# Dev_Brd_ATSAML10D16A.net
KiCad netlist of a schematic drawn in Altium Designer
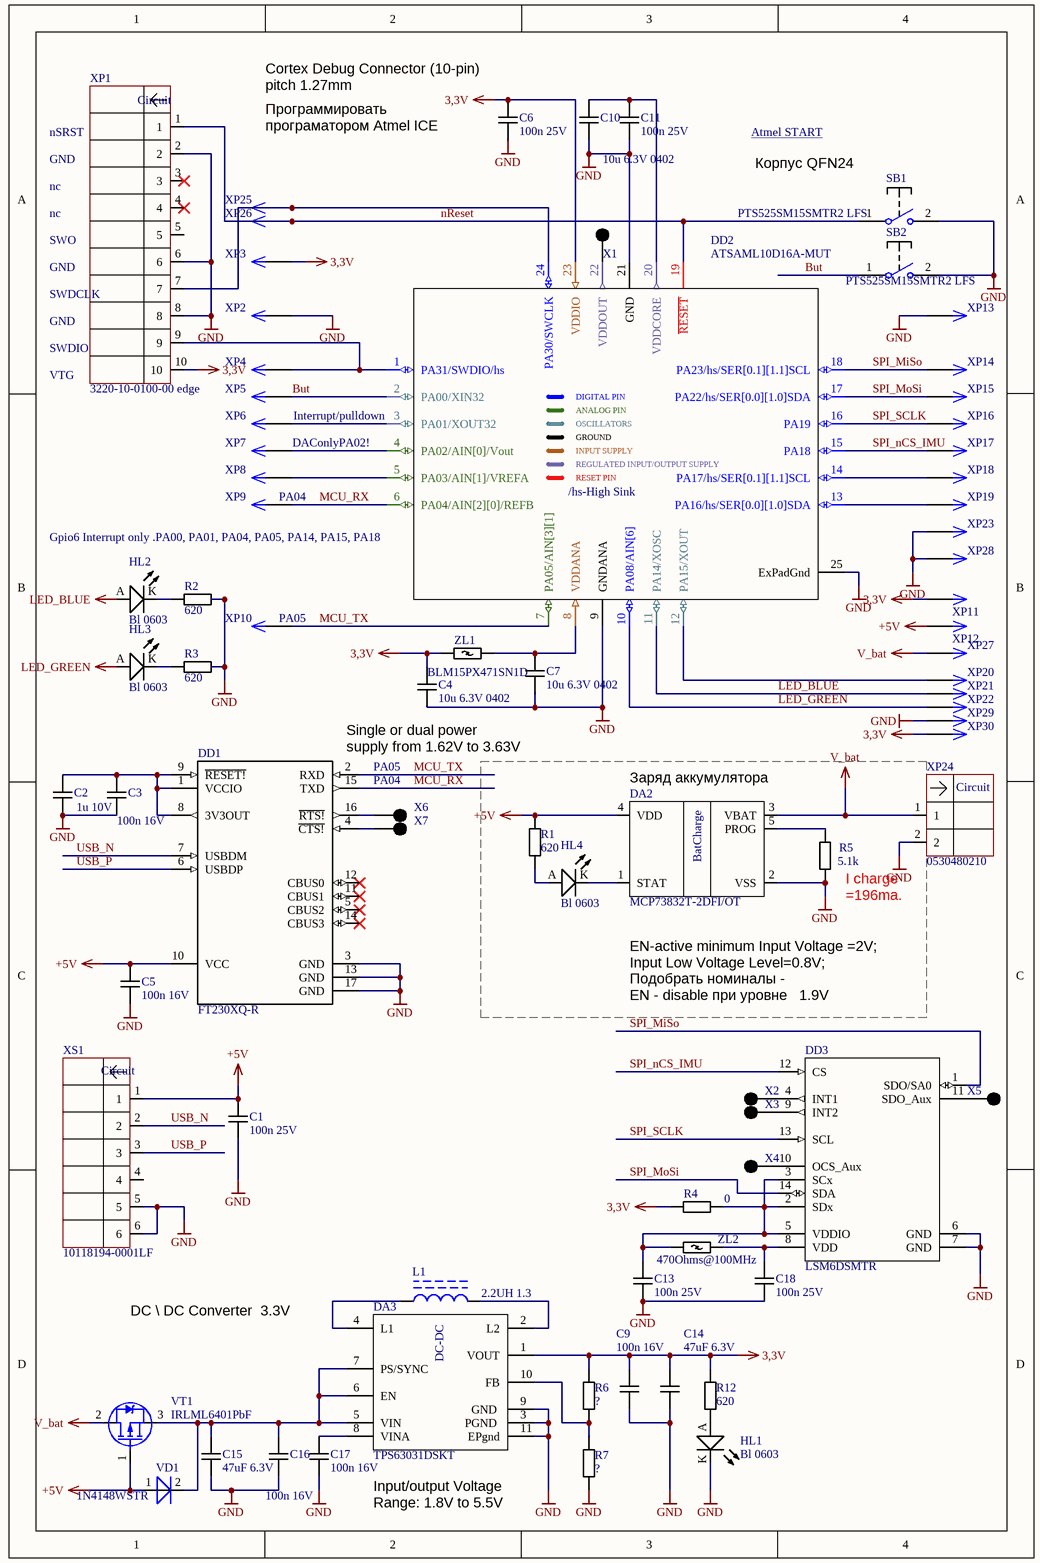
[diagram p0: Dev_Brd_ATSAML10D16A.SchDoc]

(export (version "E")
  (design (tool "Eeschema 10.0.6"))
  (components
    (comp (ref "C1")
      (value "100n 25V")
      (footprint "CapKemet1005(0402)")
      (description "CAP CER 0.1UF 25V X5R 0402")
      (fields
        (field (name "PART NUMBER") "CAPC1608(0603)")
        (field (name "DIGI-KEY PART NUMBER") "732-7495-1-ND")
      )
      (libsource (lib "") (part "Cap_1"))
    )
    (comp (ref "C2")
      (value "1u 10V")
      (footprint "CapKemet1005(0402)")
      (description "CAP CER 1UF 10V 10% X6S 0402")
      (fields
        (field (name "PART NUMBER") "CAPC1005(0402)N")
        (field (name "MANUFACTURER PART NUMBER") "LMK105BJ105KPLF")
      )
      (libsource (lib "") (part "Cap_1"))
    )
    (comp (ref "C3")
      (value "100n 16V")
      (footprint "CapKemet1005(0402)")
      (description "Cap Cer 0.1uF 16V 1% C0G(NP0) MLCC")
      (fields
        (field (name "PART NUMBER") "CL05F104ZO5NNNC")
        (field (name "DIGI-KEY PART NUMBER") "1276-1004-1-ND")
      )
      (libsource (lib "SssAccesDatbase") (part "Cap"))
    )
    (comp (ref "C4")
      (value "10u 6.3V 0402")
      (footprint "CapKemet1005(0402)")
      (description "CAP CER 10UF 6.3V X5R 0402")
      (fields
        (field (name "PART NUMBER") "CAPC1608(0603)")
        (field (name "DIGI-KEY PART NUMBER") "GRJ155R60J106ME11D")
      )
      (libsource (lib "SssAccesDatbase") (part "Cap"))
    )
    (comp (ref "C5")
      (value "100n 16V")
      (footprint "CapKemet1005(0402)")
      (description "Cap Cer 0.1uF 16V 1% C0G(NP0) MLCC")
      (fields
        (field (name "PART NUMBER") "CL05F104ZO5NNNC")
        (field (name "DIGI-KEY PART NUMBER") "1276-1004-1-ND")
      )
      (libsource (lib "SssAccesDatbase") (part "Cap"))
    )
    (comp (ref "C6")
      (value "100n 25V")
      (footprint "CapKemet1005(0402)")
      (description "CAP CER 0.1UF 25V X5R 0402")
      (fields
        (field (name "PART NUMBER") "CAPC1608(0603)")
        (field (name "DIGI-KEY PART NUMBER") "732-7495-1-ND")
      )
      (libsource (lib "") (part "Cap_1"))
    )
    (comp (ref "C7")
      (value "10u 6.3V 0402")
      (footprint "CapKemet1005(0402)")
      (description "CAP CER 10UF 6.3V X5R 0402")
      (fields
        (field (name "PART NUMBER") "CAPC1608(0603)")
        (field (name "DIGI-KEY PART NUMBER") "GRJ155R60J106ME11D")
      )
      (libsource (lib "SssAccesDatbase") (part "Cap"))
    )
    (comp (ref "C9")
      (value "100n 16V")
      (footprint "CapKemet1005(0402)")
      (description "Cap Cer 0.1uF 16V 1% C0G(NP0) MLCC")
      (fields
        (field (name "PART NUMBER") "CL05F104ZO5NNNC")
        (field (name "DIGI-KEY PART NUMBER") "1276-1004-1-ND")
      )
      (libsource (lib "SssAccesDatbase") (part "Cap"))
    )
    (comp (ref "C10")
      (value "10u 6.3V 0402")
      (footprint "CapKemet1005(0402)")
      (description "CAP CER 10UF 6.3V X5R 0402")
      (fields
        (field (name "PART NUMBER") "CAPC1608(0603)")
        (field (name "DIGI-KEY PART NUMBER") "GRJ155R60J106ME11D")
      )
      (libsource (lib "SssAccesDatbase") (part "Cap"))
    )
    (comp (ref "C11")
      (value "100n 25V")
      (footprint "CapKemet1005(0402)")
      (description "CAP CER 0.1UF 25V X5R 0402")
      (fields
        (field (name "PART NUMBER") "CAPC1608(0603)")
        (field (name "DIGI-KEY PART NUMBER") "732-7495-1-ND")
      )
      (libsource (lib "") (part "Cap_1"))
    )
    (comp (ref "C13")
      (value "100n 25V")
      (footprint "CapKemet1005(0402)")
      (description "CAP CER 0.1UF 25V X7R 0402")
      (fields
        (field (name "PART NUMBER") "CL05B104KA5NNNC")
        (field (name "DIGI-KEY PART NUMBER") "1276-6720-1-ND")
      )
      (libsource (lib "SssAccesDatbase") (part "Cap"))
    )
    (comp (ref "C14")
      (value "47uF 6.3V")
      (footprint "CapKemet1005(0402)")
      (description "CAP CER 47UF 6.3V X5R 0603")
      (fields
        (field (name "PART NUMBER") "GRM188R60J476ME15D")
        (field (name "DIGI-KEY PART NUMBER") "490-13247-1-ND")
      )
      (libsource (lib "SssAccesDatbase") (part "Cap"))
    )
    (comp (ref "C15")
      (value "47uF 6.3V")
      (footprint "CapKemet1005(0402)")
      (description "CAP CER 47UF 6.3V X5R 0603")
      (fields
        (field (name "PART NUMBER") "GRM188R60J476ME15D")
        (field (name "DIGI-KEY PART NUMBER") "490-13247-1-ND")
      )
      (libsource (lib "SssAccesDatbase") (part "Cap"))
    )
    (comp (ref "C16")
      (value "100n 16V")
      (footprint "CapKemet1005(0402)")
      (description "Cap Cer 0.1uF 16V 1% C0G(NP0) MLCC")
      (fields
        (field (name "PART NUMBER") "CL05F104ZO5NNNC")
        (field (name "DIGI-KEY PART NUMBER") "1276-1004-1-ND")
      )
      (libsource (lib "SssAccesDatbase") (part "Cap"))
    )
    (comp (ref "C17")
      (value "100n 16V")
      (footprint "CapKemet1005(0402)")
      (description "Cap Cer 0.1uF 16V 1% C0G(NP0) MLCC")
      (fields
        (field (name "PART NUMBER") "CL05F104ZO5NNNC")
        (field (name "DIGI-KEY PART NUMBER") "1276-1004-1-ND")
      )
      (libsource (lib "SssAccesDatbase") (part "Cap"))
    )
    (comp (ref "C18")
      (value "100n 25V")
      (footprint "CapKemet1005(0402)")
      (description "CAP CER 0.1UF 25V X7R 0402")
      (fields
        (field (name "PART NUMBER") "CL05B104KA5NNNC")
        (field (name "DIGI-KEY PART NUMBER") "1276-6720-1-ND")
      )
      (libsource (lib "SssAccesDatbase") (part "Cap"))
    )
    (comp (ref "DA2")
      (value "MCP73832T-2DFI/OT")
      (footprint "SOT-23-5")
      (description "IC LI-ION/LI-POLY CTRLR SOT23-5")
      (fields (field (name "DIGI-KEY PART NUMBER") "MCP73832T-2DFI/OTCT-ND"))
      (libsource (lib "SssAccesDatbase") (part "MCP73832T-2DFI/OT"))
    )
    (comp (ref "DA3")
      (value "TPS63031DSKT")
      (footprint "WSON-10")
      (description "IC REG BCK BST 3.3V 900MA 10SON")
      (fields (field (name "DIGI-KEY PART NUMBER") "296-23904-1-ND"))
      (libsource (lib "SssAccesDatbase") (part "TPS63031DSKR"))
    )
    (comp (ref "DD1")
      (value "FT230XQ-R")
      (footprint "QFN-16(4x4)")
      (description "IC USB SERIAL BASIC UART 16QFN")
      (fields (field (name "DIGI-KEY PART NUMBER") "768-1130-1-ND"))
      (libsource (lib "SssAccesDatbase") (part "FT230XQ-R"))
    )
    (comp (ref "DD2")
      (value "ATSAML10D16A-MUT")
      (footprint "VQFN-24")
      (description "IC MCU 32BIT 64KB FLASH 24VQFN,ARM® Cortex®-M23")
      (fields (field (name "DIGI-KEY PART NUMBER") "ATSAML10D16A-MUTCT-ND"))
      (libsource (lib "SssAccesDatbase") (part "ATSAML10D16A-MUT"))
    )
    (comp (ref "DD3")
      (value "LSM6DSMTR")
      (footprint "LGA-14L_2P5X3X0P83_STM-M")
      (description "IMU ACCEL/GYRO I2C/SPI 14LGA")
      (fields
        (field (name "DIGI-KEY PART NUMBER") "497-16696-1-ND")
        (field (name "MOUSER PART NUMBER") "511-LSM6DSMTR")
        (field (name "COPYRIGHT") "Copyright (C) 2018 Accelerated Designs. All rights reserved")
      )
      (libsource (lib "SssAccesDatbase") (part "LSM6DSMTR"))
    )
    (comp (ref "HL1")
      (value "Bl 0603")
      (footprint "LED-0603-BLUE")
      (description "LED BLUE DIFFUSED 0603 SMD")
      (fields
        (field (name "PART NUMBER") "150060BS55040")
        (field (name "DIGI-KEY PART NUMBER") "732-12013-1-ND")
      )
      (libsource (lib "SssAccesDatbase") (part "LED_AK"))
    )
    (comp (ref "HL2")
      (value "Bl 0603")
      (footprint "LED-0603-BLUE")
      (description "LED BLUE DIFFUSED 0603 SMD")
      (fields
        (field (name "PART NUMBER") "150060BS55040")
        (field (name "DIGI-KEY PART NUMBER") "732-12013-1-ND")
      )
      (libsource (lib "SssAccesDatbase") (part "LED_AK"))
    )
    (comp (ref "HL3")
      (value "Bl 0603")
      (footprint "LED-0603-BLUE")
      (description "LED BLUE DIFFUSED 0603 SMD")
      (fields
        (field (name "PART NUMBER") "150060BS55040")
        (field (name "DIGI-KEY PART NUMBER") "732-12013-1-ND")
      )
      (libsource (lib "SssAccesDatbase") (part "LED_AK"))
    )
    (comp (ref "HL4")
      (value "Bl 0603")
      (footprint "LED-0603-BLUE")
      (description "LED BLUE DIFFUSED 0603 SMD")
      (fields
        (field (name "PART NUMBER") "150060BS55040")
        (field (name "DIGI-KEY PART NUMBER") "732-12013-1-ND")
      )
      (libsource (lib "SssAccesDatbase") (part "LED_AK"))
    )
    (comp (ref "L1")
      (value "2.2UH 1.3")
      (footprint "CDRH2D11")
      (description "FIXED IND 2.2UH 1.3A 120 MOHM")
      (fields
        (field (name "PART NUMBER") "CDRH2D11/HPNP-2R2NC")
        (field (name "DIGI-KEY PART NUMBER") "308-1578-1-ND")
        (field (name "PUBLISHER") "Altium Limited")
      )
      (libsource (lib "SssAccesDatbase") (part "Inductor ferrite"))
    )
    (comp (ref "R1")
      (value "620")
      (footprint "REZKemet 0402")
      (fields (field (name "PART NUMBER") "RESC1005(0402)"))
      (libsource (lib "SssAccesDatbase") (part "Resistor general"))
    )
    (comp (ref "R2")
      (value "620")
      (footprint "REZKemet 0402")
      (fields (field (name "PART NUMBER") "RESC1005(0402)"))
      (libsource (lib "") (part "Resistor general_1"))
    )
    (comp (ref "R3")
      (value "620")
      (footprint "REZKemet 0402")
      (fields (field (name "PART NUMBER") "RESC1005(0402)"))
      (libsource (lib "") (part "Resistor general_1"))
    )
    (comp (ref "R4")
      (value "0")
      (footprint "REZKemet 0402")
      (description "RES SMD 0402 0 Ohm")
      (fields
        (field (name "PART NUMBER") "RMCF0402ZT0R00")
        (field (name "MOUSER PART NUMBER") "RMCF0402ZT0R00CT-ND")
      )
      (libsource (lib "") (part "Resistor general_1"))
    )
    (comp (ref "R5")
      (value "5.1k")
      (footprint "REZKemet 0402")
      (description "RES SMD 5.1K OHM 1% 1/10W 0402")
      (fields
        (field (name "PART NUMBER") "RESC1005(0402)")
        (field (name "MANUFACTURER PART NUMBER") "ERJ-2RKF5101X")
      )
      (libsource (lib "") (part "Resistor general_2"))
    )
    (comp (ref "R6")
      (value "?")
      (footprint "REZKemet 0402")
      (fields (field (name "PART NUMBER") "RESC1005(0402)"))
      (libsource (lib "SssAccesDatbase") (part "Resistor general"))
    )
    (comp (ref "R7")
      (value "?")
      (footprint "REZKemet 0402")
      (fields (field (name "PART NUMBER") "RESC1005(0402)"))
      (libsource (lib "SssAccesDatbase") (part "Resistor general"))
    )
    (comp (ref "R12")
      (value "620")
      (footprint "REZKemet 0402")
      (fields (field (name "PART NUMBER") "RESC1005(0402)"))
      (libsource (lib "SssAccesDatbase") (part "Resistor general"))
    )
    (comp (ref "SB1")
      (value "PTS525SM15SMTR2 LFS")
      (footprint "TACT_SWITCH KPT1187B")
      (description "SWITCH TACTILE SPST-NO 0.02A 15V")
      (fields (field (name "DIGI-KEY PART NUMBER") "CKN9104CT-ND"))
      (libsource (lib "SssAccesDatbase") (part "TACT_SWITCH KPT1187B"))
    )
    (comp (ref "SB2")
      (value "PTS525SM15SMTR2 LFS")
      (footprint "TACT_SWITCH KPT1187B")
      (description "SWITCH TACTILE SPST-NO 0.02A 15V")
      (fields (field (name "DIGI-KEY PART NUMBER") "CKN9104CT-ND"))
      (libsource (lib "SssAccesDatbase") (part "TACT_SWITCH KPT1187B"))
    )
    (comp (ref "VD1")
      (value "1N4148WSTR")
      (footprint "SOD323")
      (description "DIODE GEN PURP 75V 300MA SOD323")
      (fields
        (field (name "DIGI-KEY PART NUMBER") "1655-1359-1-ND")
        (field (name "MANUFACTURER PART NUMBER") "?")
        (field (name "PUBLISHER") "Altium Limited")
      )
      (libsource (lib "SssAccesDatbase") (part "Diode"))
    )
    (comp (ref "VT1")
      (value "IRLML6401PbF")
      (footprint "SOT23-3N")
      (fields (field (name "DIGI-KEY PART NUMBER") "???"))
      (libsource (lib "SssAccesDatbase") (part "TRANS-P-Channel-GDS"))
    )
    (comp (ref "X1")
      (value "PLLS1.27-1-TOP-R")
      (footprint "PLLS1.27-1-TOP-R")
      (libsource (lib "SssAccesDatbase") (part "X1_1"))
    )
    (comp (ref "X2")
      (value "PLLS1.27-1-TOP-R")
      (footprint "PLLS1.27-1-TOP-R")
      (libsource (lib "SssAccesDatbase") (part "X1_1"))
    )
    (comp (ref "X3")
      (value "PLLS1.27-1-TOP-R")
      (footprint "PLLS1.27-1-TOP-R")
      (libsource (lib "SssAccesDatbase") (part "X1_1"))
    )
    (comp (ref "X4")
      (value "PLLS1.27-1-TOP-R")
      (footprint "PLLS1.27-1-TOP-R")
      (libsource (lib "SssAccesDatbase") (part "X1_1"))
    )
    (comp (ref "X5")
      (value "PLLS1.27-1-TOP-R")
      (footprint "PLLS1.27-1-TOP-R")
      (libsource (lib "SssAccesDatbase") (part "X1_1"))
    )
    (comp (ref "X6")
      (value "PLLS1.27-1-TOP-R")
      (footprint "PLLS1.27-1-TOP-R")
      (libsource (lib "SssAccesDatbase") (part "X1_1"))
    )
    (comp (ref "X7")
      (value "PLLS1.27-1-TOP-R")
      (footprint "PLLS1.27-1-TOP-R")
      (libsource (lib "SssAccesDatbase") (part "X1_1"))
    )
    (comp (ref "XP1")
      (value "3220-10-0100-00 edge")
      (footprint "IPS 10(1.27)edge")
      (description "3220-10-0100-00")
      (fields (field (name "DIGI-KEY PART NUMBER") "1175-1627-ND"))
      (libsource (lib "SssAccesDatbase") (part "XP-10"))
    )
    (comp (ref "XP2")
      (value "PLS-1")
      (footprint "PLS-1-3D")
      (description "CONN HEADER VERT 1POS")
      (fields
        (field (name "DIGI-KEY PART NUMBER") "S1011EC-01-ND")
        (field (name "MANUFACTURER PART NUMBER") "PRPC001SAAN-RC")
      )
      (libsource (lib "SssAccesDatbase") (part "XP-1_1"))
    )
    (comp (ref "XP3")
      (value "PLS-1")
      (footprint "PLS-1-3D")
      (description "CONN HEADER VERT 1POS")
      (fields
        (field (name "DIGI-KEY PART NUMBER") "S1011EC-01-ND")
        (field (name "MANUFACTURER PART NUMBER") "PRPC001SAAN-RC")
      )
      (libsource (lib "SssAccesDatbase") (part "XP-1_1"))
    )
    (comp (ref "XP4")
      (value "PLS-1")
      (footprint "PLS-1-3D")
      (description "CONN HEADER VERT 1POS")
      (fields
        (field (name "DIGI-KEY PART NUMBER") "S1011EC-01-ND")
        (field (name "MANUFACTURER PART NUMBER") "PRPC001SAAN-RC")
      )
      (libsource (lib "SssAccesDatbase") (part "XP-1_1"))
    )
    (comp (ref "XP5")
      (value "PLS-1")
      (footprint "PLS-1-3D")
      (description "CONN HEADER VERT 1POS")
      (fields
        (field (name "DIGI-KEY PART NUMBER") "S1011EC-01-ND")
        (field (name "MANUFACTURER PART NUMBER") "PRPC001SAAN-RC")
      )
      (libsource (lib "SssAccesDatbase") (part "XP-1_1"))
    )
    (comp (ref "XP6")
      (value "PLS-1")
      (footprint "PLS-1-3D")
      (description "CONN HEADER VERT 1POS")
      (fields
        (field (name "DIGI-KEY PART NUMBER") "S1011EC-01-ND")
        (field (name "MANUFACTURER PART NUMBER") "PRPC001SAAN-RC")
      )
      (libsource (lib "SssAccesDatbase") (part "XP-1_1"))
    )
    (comp (ref "XP7")
      (value "PLS-1")
      (footprint "PLS-1-3D")
      (description "CONN HEADER VERT 1POS")
      (fields
        (field (name "DIGI-KEY PART NUMBER") "S1011EC-01-ND")
        (field (name "MANUFACTURER PART NUMBER") "PRPC001SAAN-RC")
      )
      (libsource (lib "SssAccesDatbase") (part "XP-1_1"))
    )
    (comp (ref "XP8")
      (value "PLS-1")
      (footprint "PLS-1-3D")
      (description "CONN HEADER VERT 1POS")
      (fields
        (field (name "DIGI-KEY PART NUMBER") "S1011EC-01-ND")
        (field (name "MANUFACTURER PART NUMBER") "PRPC001SAAN-RC")
      )
      (libsource (lib "SssAccesDatbase") (part "XP-1_1"))
    )
    (comp (ref "XP9")
      (value "PLS-1")
      (footprint "PLS-1-3D")
      (description "CONN HEADER VERT 1POS")
      (fields
        (field (name "DIGI-KEY PART NUMBER") "S1011EC-01-ND")
        (field (name "MANUFACTURER PART NUMBER") "PRPC001SAAN-RC")
      )
      (libsource (lib "SssAccesDatbase") (part "XP-1_1"))
    )
    (comp (ref "XP10")
      (value "PLS-1")
      (footprint "PLS-1-3D")
      (description "CONN HEADER VERT 1POS")
      (fields
        (field (name "DIGI-KEY PART NUMBER") "S1011EC-01-ND")
        (field (name "MANUFACTURER PART NUMBER") "PRPC001SAAN-RC")
      )
      (libsource (lib "SssAccesDatbase") (part "XP-1_1"))
    )
    (comp (ref "XP11")
      (value "PLS-1")
      (footprint "PLS-1-3D")
      (description "CONN HEADER VERT 1POS")
      (fields
        (field (name "DIGI-KEY PART NUMBER") "S1011EC-01-ND")
        (field (name "MANUFACTURER PART NUMBER") "PRPC001SAAN-RC")
      )
      (libsource (lib "SssAccesDatbase") (part "XP-1_1"))
    )
    (comp (ref "XP12")
      (value "PLS-1")
      (footprint "PLS-1-3D")
      (description "CONN HEADER VERT 1POS")
      (fields
        (field (name "DIGI-KEY PART NUMBER") "S1011EC-01-ND")
        (field (name "MANUFACTURER PART NUMBER") "PRPC001SAAN-RC")
      )
      (libsource (lib "SssAccesDatbase") (part "XP-1_1"))
    )
    (comp (ref "XP13")
      (value "PLS-1")
      (footprint "PLS-1-3D")
      (description "CONN HEADER VERT 1POS")
      (fields
        (field (name "DIGI-KEY PART NUMBER") "S1011EC-01-ND")
        (field (name "MANUFACTURER PART NUMBER") "PRPC001SAAN-RC")
      )
      (libsource (lib "SssAccesDatbase") (part "XP-1_1"))
    )
    (comp (ref "XP14")
      (value "PLS-1")
      (footprint "PLS-1-3D")
      (description "CONN HEADER VERT 1POS")
      (fields
        (field (name "DIGI-KEY PART NUMBER") "S1011EC-01-ND")
        (field (name "MANUFACTURER PART NUMBER") "PRPC001SAAN-RC")
      )
      (libsource (lib "SssAccesDatbase") (part "XP-1_1"))
    )
    (comp (ref "XP15")
      (value "PLS-1")
      (footprint "PLS-1-3D")
      (description "CONN HEADER VERT 1POS")
      (fields
        (field (name "DIGI-KEY PART NUMBER") "S1011EC-01-ND")
        (field (name "MANUFACTURER PART NUMBER") "PRPC001SAAN-RC")
      )
      (libsource (lib "SssAccesDatbase") (part "XP-1_1"))
    )
    (comp (ref "XP16")
      (value "PLS-1")
      (footprint "PLS-1-3D")
      (description "CONN HEADER VERT 1POS")
      (fields
        (field (name "DIGI-KEY PART NUMBER") "S1011EC-01-ND")
        (field (name "MANUFACTURER PART NUMBER") "PRPC001SAAN-RC")
      )
      (libsource (lib "SssAccesDatbase") (part "XP-1_1"))
    )
    (comp (ref "XP17")
      (value "PLS-1")
      (footprint "PLS-1-3D")
      (description "CONN HEADER VERT 1POS")
      (fields
        (field (name "DIGI-KEY PART NUMBER") "S1011EC-01-ND")
        (field (name "MANUFACTURER PART NUMBER") "PRPC001SAAN-RC")
      )
      (libsource (lib "SssAccesDatbase") (part "XP-1_1"))
    )
    (comp (ref "XP18")
      (value "PLS-1")
      (footprint "PLS-1-3D")
      (description "CONN HEADER VERT 1POS")
      (fields
        (field (name "DIGI-KEY PART NUMBER") "S1011EC-01-ND")
        (field (name "MANUFACTURER PART NUMBER") "PRPC001SAAN-RC")
      )
      (libsource (lib "SssAccesDatbase") (part "XP-1_1"))
    )
    (comp (ref "XP19")
      (value "PLS-1")
      (footprint "PLS-1-3D")
      (description "CONN HEADER VERT 1POS")
      (fields
        (field (name "DIGI-KEY PART NUMBER") "S1011EC-01-ND")
        (field (name "MANUFACTURER PART NUMBER") "PRPC001SAAN-RC")
      )
      (libsource (lib "SssAccesDatbase") (part "XP-1_1"))
    )
    (comp (ref "XP20")
      (value "PLS-1")
      (footprint "PLS-1-3D")
      (description "CONN HEADER VERT 1POS")
      (fields
        (field (name "DIGI-KEY PART NUMBER") "S1011EC-01-ND")
        (field (name "MANUFACTURER PART NUMBER") "PRPC001SAAN-RC")
      )
      (libsource (lib "SssAccesDatbase") (part "XP-1_1"))
    )
    (comp (ref "XP21")
      (value "PLS-1")
      (footprint "PLS-1-3D")
      (description "CONN HEADER VERT 1POS")
      (fields
        (field (name "DIGI-KEY PART NUMBER") "S1011EC-01-ND")
        (field (name "MANUFACTURER PART NUMBER") "PRPC001SAAN-RC")
      )
      (libsource (lib "SssAccesDatbase") (part "XP-1_1"))
    )
    (comp (ref "XP22")
      (value "PLS-1")
      (footprint "PLS-1-3D")
      (description "CONN HEADER VERT 1POS")
      (fields
        (field (name "DIGI-KEY PART NUMBER") "S1011EC-01-ND")
        (field (name "MANUFACTURER PART NUMBER") "PRPC001SAAN-RC")
      )
      (libsource (lib "SssAccesDatbase") (part "XP-1_1"))
    )
    (comp (ref "XP23")
      (value "PLS-1")
      (footprint "PLS-1-3D")
      (description "CONN HEADER VERT 1POS")
      (fields
        (field (name "DIGI-KEY PART NUMBER") "S1011EC-01-ND")
        (field (name "MANUFACTURER PART NUMBER") "PRPC001SAAN-RC")
      )
      (libsource (lib "SssAccesDatbase") (part "XP-1_1"))
    )
    (comp (ref "XP24")
      (value "0530480210")
      (footprint "0530480210")
      (description "CONN HEADER R/A 2POS 1.25MM")
      (fields (field (name "DIGI-KEY PART NUMBER") "WM1742-ND"))
      (libsource (lib "SssAccesDatbase") (part "XP-2"))
    )
    (comp (ref "XP25")
      (value "PLS-1")
      (footprint "PLS-1-3D")
      (description "CONN HEADER VERT 1POS")
      (fields
        (field (name "DIGI-KEY PART NUMBER") "S1011EC-01-ND")
        (field (name "MANUFACTURER PART NUMBER") "PRPC001SAAN-RC")
      )
      (libsource (lib "SssAccesDatbase") (part "XP-1_1"))
    )
    (comp (ref "XP26")
      (value "PLS-1")
      (footprint "PLS-1-3D")
      (description "CONN HEADER VERT 1POS")
      (fields
        (field (name "DIGI-KEY PART NUMBER") "S1011EC-01-ND")
        (field (name "MANUFACTURER PART NUMBER") "PRPC001SAAN-RC")
      )
      (libsource (lib "SssAccesDatbase") (part "XP-1_1"))
    )
    (comp (ref "XP27")
      (value "PLS-1")
      (footprint "PLS-1-3D")
      (description "CONN HEADER VERT 1POS")
      (fields
        (field (name "DIGI-KEY PART NUMBER") "S1011EC-01-ND")
        (field (name "MANUFACTURER PART NUMBER") "PRPC001SAAN-RC")
      )
      (libsource (lib "SssAccesDatbase") (part "XP-1_1"))
    )
    (comp (ref "XP28")
      (value "PLS-1")
      (footprint "PLS-1-3D")
      (description "CONN HEADER VERT 1POS")
      (fields
        (field (name "DIGI-KEY PART NUMBER") "S1011EC-01-ND")
        (field (name "MANUFACTURER PART NUMBER") "PRPC001SAAN-RC")
      )
      (libsource (lib "SssAccesDatbase") (part "XP-1_1"))
    )
    (comp (ref "XP29")
      (value "PLS-1")
      (footprint "PLS-1-3D")
      (description "CONN HEADER VERT 1POS")
      (fields
        (field (name "DIGI-KEY PART NUMBER") "S1011EC-01-ND")
        (field (name "MANUFACTURER PART NUMBER") "PRPC001SAAN-RC")
      )
      (libsource (lib "SssAccesDatbase") (part "XP-1_1"))
    )
    (comp (ref "XP30")
      (value "PLS-1")
      (footprint "PLS-1-3D")
      (description "CONN HEADER VERT 1POS")
      (fields
        (field (name "DIGI-KEY PART NUMBER") "S1011EC-01-ND")
        (field (name "MANUFACTURER PART NUMBER") "PRPC001SAAN-RC")
      )
      (libsource (lib "SssAccesDatbase") (part "XP-1_1"))
    )
    (comp (ref "XS1")
      (value "10118194-0001LF")
      (footprint "MICRO_USB _B")
      (description "USB Connectors 5P MICRO USB TYPE B RCPT W/ REAR PEGS")
      (fields
        (field (name "DIGI-KEY PART NUMBER") "609-4618-1-ND")
        (field (name "MOUSER PART NUMBER") "649-10118194-0001LF")
      )
      (libsource (lib "SssAccesDatbase") (part "Micro USB"))
    )
    (comp (ref "ZL1")
      (value "BLM15PX471SN1D")
      (footprint "Ferrite1005(0402)")
      (description "FERRITE BEAD 470 OHM 0402 1LN")
      (fields
        (field (name "PART NUMBER") "Ferrite1005(0402)")
        (field (name "DIGI-KEY PART NUMBER") "490-10662-1-ND")
      )
      (libsource (lib "SssAccesDatbase") (part "ZL"))
    )
    (comp (ref "ZL2")
      (value "470Ohms@100MHz")
      (footprint "Ferrite1005(0402)")
      (description "FERRITE BEAD 470 OHM 0402 1LN")
      (fields
        (field (name "PART NUMBER") "Ferrite1005(0402)")
        (field (name "MANUFACTURER PART NUMBER") "BLM15PX471SN1D")
      )
      (libsource (lib "SssAccesDatbase") (part "ZL"))
    )
  )
  (nets
    (net (code "1") (name "+5V") (class "Default")
      (node (ref "C1") (pin "1") (pinfunction "1_1") (pintype "passive"))
      (node (ref "C5") (pin "2") (pinfunction "2_2") (pintype "passive"))
      (node (ref "DA2") (pin "4") (pinfunction "VDD_4") (pintype "passive"))
      (node (ref "DD1") (pin "10") (pinfunction "VCC_10") (pintype "power_in"))
      (node (ref "R1") (pin "2") (pinfunction "2_2") (pintype "passive"))
      (node (ref "VD1") (pin "1") (pintype "passive"))
      (node (ref "VT1") (pin "1") (pinfunction "G_1") (pintype "passive"))
      (node (ref "XP12") (pin "1") (pinfunction "1_1") (pintype "passive"))
      (node (ref "XS1") (pin "1") (pinfunction "1_1") (pintype "passive"))
    )
    (net (code "2") (name "/But") (class "Default")
      (node (ref "DD2") (pin "2") (pinfunction "PA00/XIN32_2") (pintype "bidirectional"))
      (node (ref "SB2") (pin "1") (pinfunction "COMMON_1") (pintype "passive"))
      (node (ref "XP5") (pin "1") (pinfunction "1_1") (pintype "passive"))
    )
    (net (code "3") (name "/MCU_RX") (class "Default")
      (node (ref "DD1") (pin "15") (pinfunction "TXD_15") (pintype "output"))
      (node (ref "DD2") (pin "6") (pinfunction "PA04/AIN[2][0]/REFB_6") (pintype "bidirectional"))
      (node (ref "XP9") (pin "1") (pinfunction "1_1") (pintype "passive"))
    )
    (net (code "4") (name "/MCU_TX") (class "Default")
      (node (ref "DD1") (pin "2") (pinfunction "RXD_2") (pintype "input"))
      (node (ref "DD2") (pin "7") (pinfunction "PA05/AIN[3][1]_7") (pintype "bidirectional"))
      (node (ref "XP10") (pin "1") (pinfunction "1_1") (pintype "passive"))
    )
    (net (code "5") (name "/SPI_MiSo") (class "Default")
      (node (ref "DD2") (pin "18") (pinfunction "PA23/hs/SER[0.1][1.1]SCL_18") (pintype "bidirectional"))
      (node (ref "DD3") (pin "1") (pinfunction "SDO/SA0_1") (pintype "bidirectional"))
      (node (ref "XP14") (pin "1") (pinfunction "1_1") (pintype "passive"))
    )
    (net (code "6") (name "/SPI_MoSi") (class "Default")
      (node (ref "DD2") (pin "17") (pinfunction "PA22/hs/SER[0.0][1.0]SDA_17") (pintype "bidirectional"))
      (node (ref "DD3") (pin "14") (pinfunction "SDA_14") (pintype "bidirectional"))
      (node (ref "XP15") (pin "1") (pinfunction "1_1") (pintype "passive"))
    )
    (net (code "7") (name "/SPI_SCLK") (class "Default")
      (node (ref "DD2") (pin "16") (pinfunction "PA19_16") (pintype "bidirectional"))
      (node (ref "DD3") (pin "13") (pinfunction "SCL_13") (pintype "input"))
      (node (ref "XP16") (pin "1") (pinfunction "1_1") (pintype "passive"))
    )
    (net (code "8") (name "/SPI_nCS_IMU") (class "Default")
      (node (ref "DD2") (pin "15") (pinfunction "PA18_15") (pintype "bidirectional"))
      (node (ref "DD3") (pin "12") (pinfunction "CS_12") (pintype "input"))
      (node (ref "XP17") (pin "1") (pinfunction "1_1") (pintype "passive"))
    )
    (net (code "9") (name "/USB_N") (class "Default")
      (node (ref "DD1") (pin "7") (pinfunction "USBDM_7") (pintype "input"))
      (node (ref "XS1") (pin "2") (pinfunction "2_2") (pintype "passive"))
    )
    (net (code "10") (name "/USB_P") (class "Default")
      (node (ref "DD1") (pin "6") (pinfunction "USBDP_6") (pintype "input"))
      (node (ref "XS1") (pin "3") (pinfunction "3_3") (pintype "passive"))
    )
    (net (code "11") (name "/nReset") (class "Default")
      (node (ref "DD2") (pin "19") (pinfunction "~{RESET}_19") (pintype "passive"))
      (node (ref "SB1") (pin "1") (pinfunction "COMMON_1") (pintype "passive"))
      (node (ref "XP1") (pin "1") (pinfunction "1_1") (pintype "passive"))
      (node (ref "XP26") (pin "1") (pinfunction "1_1") (pintype "passive"))
    )
    (net (code "12") (name "3,3V") (class "Default")
      (node (ref "C14") (pin "2") (pinfunction "2_2") (pintype "passive"))
      (node (ref "C4") (pin "2") (pinfunction "2_2") (pintype "passive"))
      (node (ref "C6") (pin "1") (pinfunction "1_1") (pintype "passive"))
      (node (ref "C9") (pin "2") (pinfunction "2_2") (pintype "passive"))
      (node (ref "DA3") (pin "1") (pinfunction "VOUT_1") (pintype "passive"))
      (node (ref "DD2") (pin "23") (pinfunction "VDDIO_23") (pintype "input"))
      (node (ref "R12") (pin "2") (pinfunction "2_2") (pintype "passive"))
      (node (ref "R4") (pin "1") (pinfunction "1_1") (pintype "passive"))
      (node (ref "R6") (pin "2") (pinfunction "2_2") (pintype "passive"))
      (node (ref "XP1") (pin "10") (pinfunction "10_10") (pintype "passive"))
      (node (ref "XP11") (pin "1") (pinfunction "1_1") (pintype "passive"))
      (node (ref "XP3") (pin "1") (pinfunction "1_1") (pintype "passive"))
      (node (ref "XP30") (pin "1") (pinfunction "1_1") (pintype "passive"))
      (node (ref "ZL1") (pin "1") (pinfunction "1_1") (pintype "passive"))
    )
    (net (code "13") (name "GND") (class "Default")
      (node (ref "C1") (pin "2") (pinfunction "2_2") (pintype "passive"))
      (node (ref "C10") (pin "1") (pinfunction "1_1") (pintype "passive"))
      (node (ref "C11") (pin "2") (pinfunction "2_2") (pintype "passive"))
      (node (ref "C13") (pin "2") (pinfunction "2_2") (pintype "passive"))
      (node (ref "C14") (pin "1") (pinfunction "1_1") (pintype "passive"))
      (node (ref "C15") (pin "1") (pinfunction "1_1") (pintype "passive"))
      (node (ref "C16") (pin "1") (pinfunction "1_1") (pintype "passive"))
      (node (ref "C17") (pin "1") (pinfunction "1_1") (pintype "passive"))
      (node (ref "C18") (pin "2") (pinfunction "2_2") (pintype "passive"))
      (node (ref "C2") (pin "1") (pinfunction "1_1") (pintype "passive"))
      (node (ref "C3") (pin "1") (pinfunction "1_1") (pintype "passive"))
      (node (ref "C4") (pin "1") (pinfunction "1_1") (pintype "passive"))
      (node (ref "C5") (pin "1") (pinfunction "1_1") (pintype "passive"))
      (node (ref "C6") (pin "2") (pinfunction "2_2") (pintype "passive"))
      (node (ref "C7") (pin "1") (pinfunction "1_1") (pintype "passive"))
      (node (ref "C9") (pin "1") (pinfunction "1_1") (pintype "passive"))
      (node (ref "DA2") (pin "2") (pinfunction "VSS_2") (pintype "passive"))
      (node (ref "DA3") (pin "11") (pinfunction "EPgnd_11") (pintype "passive"))
      (node (ref "DA3") (pin "3") (pinfunction "PGND_3") (pintype "passive"))
      (node (ref "DA3") (pin "9") (pinfunction "GND_9") (pintype "passive"))
      (node (ref "DD1") (pin "13") (pinfunction "GND_13") (pintype "power_in"))
      (node (ref "DD1") (pin "17") (pinfunction "GND_17") (pintype "power_in"))
      (node (ref "DD1") (pin "3") (pinfunction "GND_3") (pintype "power_in"))
      (node (ref "DD2") (pin "21") (pinfunction "GND_21") (pintype "passive"))
      (node (ref "DD2") (pin "25") (pinfunction "ExPadGnd_25") (pintype "passive"))
      (node (ref "DD2") (pin "9") (pinfunction "GNDANA_9") (pintype "passive"))
      (node (ref "DD3") (pin "6") (pinfunction "GND_6") (pintype "passive"))
      (node (ref "DD3") (pin "7") (pinfunction "GND_7") (pintype "passive"))
      (node (ref "HL1") (pin "K") (pinfunction "K_K") (pintype "passive"))
      (node (ref "R2") (pin "2") (pinfunction "2_2") (pintype "passive"))
      (node (ref "R3") (pin "2") (pinfunction "2_2") (pintype "passive"))
      (node (ref "R5") (pin "2") (pinfunction "2_2") (pintype "passive"))
      (node (ref "R7") (pin "1") (pinfunction "1_1") (pintype "passive"))
      (node (ref "SB1") (pin "2") (pinfunction "NO_2") (pintype "passive"))
      (node (ref "SB2") (pin "2") (pinfunction "NO_2") (pintype "passive"))
      (node (ref "XP1") (pin "2") (pinfunction "2_2") (pintype "passive"))
      (node (ref "XP1") (pin "6") (pinfunction "6_6") (pintype "passive"))
      (node (ref "XP1") (pin "8") (pinfunction "8_8") (pintype "passive"))
      (node (ref "XP13") (pin "1") (pinfunction "1_1") (pintype "passive"))
      (node (ref "XP2") (pin "1") (pinfunction "1_1") (pintype "passive"))
      (node (ref "XP23") (pin "1") (pinfunction "1_1") (pintype "passive"))
      (node (ref "XP24") (pin "2") (pinfunction "2_2") (pintype "passive"))
      (node (ref "XP28") (pin "1") (pinfunction "1_1") (pintype "passive"))
      (node (ref "XP29") (pin "1") (pinfunction "1_1") (pintype "passive"))
      (node (ref "XS1") (pin "5") (pinfunction "5_5") (pintype "passive"))
      (node (ref "XS1") (pin "6") (pinfunction "6_6") (pintype "passive"))
    )
    (net (code "14") (name "LED_BLUE") (class "Default")
      (node (ref "DD2") (pin "11") (pinfunction "PA14/XOSC_11") (pintype "bidirectional"))
      (node (ref "HL2") (pin "A") (pinfunction "A_A") (pintype "passive"))
      (node (ref "XP21") (pin "1") (pinfunction "1_1") (pintype "passive"))
    )
    (net (code "15") (name "LED_GREEN") (class "Default")
      (node (ref "DD2") (pin "10") (pinfunction "PA08/AIN[6]_10") (pintype "bidirectional"))
      (node (ref "HL3") (pin "A") (pinfunction "A_A") (pintype "passive"))
      (node (ref "XP22") (pin "1") (pinfunction "1_1") (pintype "passive"))
    )
    (net (code "16") (name "Net-(DA2-PROG)") (class "Default")
      (node (ref "DA2") (pin "5") (pinfunction "PROG_5") (pintype "passive"))
      (node (ref "R5") (pin "1") (pinfunction "1_1") (pintype "passive"))
    )
    (net (code "17") (name "Net-(DA2-STAT)") (class "Default")
      (node (ref "DA2") (pin "1") (pinfunction "STAT_1") (pintype "passive"))
      (node (ref "HL4") (pin "K") (pinfunction "K_K") (pintype "passive"))
    )
    (net (code "18") (name "Net-(DA3-EN)") (class "Default")
      (node (ref "C15") (pin "2") (pinfunction "2_2") (pintype "passive"))
      (node (ref "C16") (pin "2") (pinfunction "2_2") (pintype "passive"))
      (node (ref "DA3") (pin "5") (pinfunction "VIN_5") (pintype "passive"))
      (node (ref "DA3") (pin "6") (pinfunction "EN_6") (pintype "passive"))
      (node (ref "DA3") (pin "7") (pinfunction "PS/SYNC_7") (pintype "passive"))
      (node (ref "VD1") (pin "2") (pintype "passive"))
      (node (ref "VT1") (pin "3") (pinfunction "S_3") (pintype "passive"))
    )
    (net (code "19") (name "Net-(DA3-FB)") (class "Default")
      (node (ref "DA3") (pin "10") (pinfunction "FB_10") (pintype "passive"))
      (node (ref "R6") (pin "1") (pinfunction "1_1") (pintype "passive"))
      (node (ref "R7") (pin "2") (pinfunction "2_2") (pintype "passive"))
    )
    (net (code "20") (name "Net-(DA3-L1)") (class "Default")
      (node (ref "DA3") (pin "4") (pinfunction "L1_4") (pintype "passive"))
      (node (ref "L1") (pin "1") (pinfunction "1_1") (pintype "passive"))
    )
    (net (code "21") (name "Net-(DA3-L2)") (class "Default")
      (node (ref "DA3") (pin "2") (pinfunction "L2_2") (pintype "passive"))
      (node (ref "L1") (pin "2") (pinfunction "2_2") (pintype "passive"))
    )
    (net (code "22") (name "Net-(DA3-VINA)") (class "Default")
      (node (ref "C17") (pin "2") (pinfunction "2_2") (pintype "passive"))
      (node (ref "DA3") (pin "8") (pinfunction "VINA_8") (pintype "passive"))
    )
    (net (code "23") (name "Net-(DD1-3V3OUT)") (class "Default")
      (node (ref "C2") (pin "2") (pinfunction "2_2") (pintype "passive"))
      (node (ref "C3") (pin "2") (pinfunction "2_2") (pintype "passive"))
      (node (ref "DD1") (pin "1") (pinfunction "VCCIO_1") (pintype "power_in"))
      (node (ref "DD1") (pin "8") (pinfunction "3V3OUT_8") (pintype "output"))
      (node (ref "DD1") (pin "9") (pinfunction "~{RESET!}_9") (pintype "input"))
    )
    (net (code "24") (name "Net-(DD1-~{CTS!})") (class "Default")
      (node (ref "DD1") (pin "4") (pinfunction "~{CTS!}_4") (pintype "input"))
      (node (ref "X7") (pin "1") (pinfunction "1_1") (pintype "passive"))
    )
    (net (code "25") (name "Net-(DD1-~{RTS!})") (class "Default")
      (node (ref "DD1") (pin "16") (pinfunction "~{RTS!}_16") (pintype "output"))
      (node (ref "X6") (pin "1") (pinfunction "1_1") (pintype "passive"))
    )
    (net (code "26") (name "Net-(DD2-PA01{slash}XOUT32)") (class "Default")
      (node (ref "DD2") (pin "3") (pinfunction "PA01/XOUT32_3") (pintype "bidirectional"))
      (node (ref "XP6") (pin "1") (pinfunction "1_1") (pintype "passive"))
    )
    (net (code "27") (name "Net-(DD2-PA02{slash}AIN[0]{slash}Vout)") (class "Default")
      (node (ref "DD2") (pin "4") (pinfunction "PA02/AIN[0]/Vout_4") (pintype "bidirectional"))
      (node (ref "XP7") (pin "1") (pinfunction "1_1") (pintype "passive"))
    )
    (net (code "28") (name "Net-(DD2-PA03{slash}AIN[1]{slash}VREFA)") (class "Default")
      (node (ref "DD2") (pin "5") (pinfunction "PA03/AIN[1]/VREFA_5") (pintype "bidirectional"))
      (node (ref "XP8") (pin "1") (pinfunction "1_1") (pintype "passive"))
    )
    (net (code "29") (name "Net-(DD2-PA15{slash}XOUT)") (class "Default")
      (node (ref "DD2") (pin "12") (pinfunction "PA15/XOUT_12") (pintype "bidirectional"))
      (node (ref "XP20") (pin "1") (pinfunction "1_1") (pintype "passive"))
    )
    (net (code "30") (name "Net-(DD2-PA16{slash}hs{slash}SER[0.0][1.0]SDA)") (class "Default")
      (node (ref "DD2") (pin "13") (pinfunction "PA16/hs/SER[0.0][1.0]SDA_13") (pintype "bidirectional"))
      (node (ref "XP19") (pin "1") (pinfunction "1_1") (pintype "passive"))
    )
    (net (code "31") (name "Net-(DD2-PA17{slash}hs{slash}SER[0.1][1.1]SCL)") (class "Default")
      (node (ref "DD2") (pin "14") (pinfunction "PA17/hs/SER[0.1][1.1]SCL_14") (pintype "bidirectional"))
      (node (ref "XP18") (pin "1") (pinfunction "1_1") (pintype "passive"))
    )
    (net (code "32") (name "Net-(DD2-PA30{slash}SWCLK)") (class "Default")
      (node (ref "DD2") (pin "24") (pinfunction "PA30/SWCLK_24") (pintype "bidirectional"))
      (node (ref "XP1") (pin "7") (pinfunction "7_7") (pintype "passive"))
      (node (ref "XP25") (pin "1") (pinfunction "1_1") (pintype "passive"))
    )
    (net (code "33") (name "Net-(DD2-PA31{slash}SWDIO{slash}hs)") (class "Default")
      (node (ref "DD2") (pin "1") (pinfunction "PA31/SWDIO/hs_1") (pintype "bidirectional"))
      (node (ref "XP1") (pin "9") (pinfunction "9_9") (pintype "passive"))
      (node (ref "XP4") (pin "1") (pinfunction "1_1") (pintype "passive"))
    )
    (net (code "34") (name "Net-(DD2-VDDANA)") (class "Default")
      (node (ref "C7") (pin "2") (pinfunction "2_2") (pintype "passive"))
      (node (ref "DD2") (pin "8") (pinfunction "VDDANA_8") (pintype "input"))
      (node (ref "ZL1") (pin "2") (pinfunction "2_2") (pintype "passive"))
    )
    (net (code "35") (name "Net-(DD2-VDDCORE)") (class "Default")
      (node (ref "C10") (pin "2") (pinfunction "2_2") (pintype "passive"))
      (node (ref "C11") (pin "1") (pinfunction "1_1") (pintype "passive"))
      (node (ref "DD2") (pin "20") (pinfunction "VDDCORE_20") (pintype "output"))
    )
    (net (code "36") (name "Net-(DD2-VDDOUT)") (class "Default")
      (node (ref "DD2") (pin "22") (pinfunction "VDDOUT_22") (pintype "output"))
      (node (ref "X1") (pin "1") (pinfunction "1_1") (pintype "passive"))
    )
    (net (code "37") (name "Net-(DD3-INT1)") (class "Default")
      (node (ref "DD3") (pin "4") (pinfunction "INT1_4") (pintype "output"))
      (node (ref "X2") (pin "1") (pinfunction "1_1") (pintype "passive"))
    )
    (net (code "38") (name "Net-(DD3-INT2)") (class "Default")
      (node (ref "DD3") (pin "9") (pinfunction "INT2_9") (pintype "output"))
      (node (ref "X3") (pin "1") (pinfunction "1_1") (pintype "passive"))
    )
    (net (code "39") (name "Net-(DD3-OCS_Aux)") (class "Default")
      (node (ref "DD3") (pin "10") (pinfunction "OCS_Aux_10") (pintype "passive"))
      (node (ref "X4") (pin "1") (pinfunction "1_1") (pintype "passive"))
    )
    (net (code "40") (name "Net-(DD3-SCx)") (class "Default")
      (node (ref "C13") (pin "1") (pinfunction "1_1") (pintype "passive"))
      (node (ref "DD3") (pin "2") (pinfunction "SDx_2") (pintype "passive"))
      (node (ref "DD3") (pin "3") (pinfunction "SCx_3") (pintype "passive"))
      (node (ref "DD3") (pin "5") (pinfunction "VDDIO_5") (pintype "power_in"))
      (node (ref "R4") (pin "2") (pinfunction "2_2") (pintype "passive"))
      (node (ref "ZL2") (pin "1") (pinfunction "1_1") (pintype "passive"))
    )
    (net (code "41") (name "Net-(DD3-SDO_Aux)") (class "Default")
      (node (ref "DD3") (pin "11") (pinfunction "SDO_Aux_11") (pintype "passive"))
      (node (ref "X5") (pin "1") (pinfunction "1_1") (pintype "passive"))
    )
    (net (code "42") (name "Net-(DD3-VDD)") (class "Default")
      (node (ref "C18") (pin "1") (pinfunction "1_1") (pintype "passive"))
      (node (ref "DD3") (pin "8") (pinfunction "VDD_8") (pintype "power_in"))
      (node (ref "ZL2") (pin "2") (pinfunction "2_2") (pintype "passive"))
    )
    (net (code "43") (name "Net-(HL1-PadA)") (class "Default")
      (node (ref "HL1") (pin "A") (pinfunction "A_A") (pintype "passive"))
      (node (ref "R12") (pin "1") (pinfunction "1_1") (pintype "passive"))
    )
    (net (code "44") (name "Net-(HL2-PadK)") (class "Default")
      (node (ref "HL2") (pin "K") (pinfunction "K_K") (pintype "passive"))
      (node (ref "R2") (pin "1") (pinfunction "1_1") (pintype "passive"))
    )
    (net (code "45") (name "Net-(HL3-PadK)") (class "Default")
      (node (ref "HL3") (pin "K") (pinfunction "K_K") (pintype "passive"))
      (node (ref "R3") (pin "1") (pinfunction "1_1") (pintype "passive"))
    )
    (net (code "46") (name "Net-(HL4-PadA)") (class "Default")
      (node (ref "HL4") (pin "A") (pinfunction "A_A") (pintype "passive"))
      (node (ref "R1") (pin "1") (pinfunction "1_1") (pintype "passive"))
    )
    (net (code "47") (name "V_bat") (class "Default")
      (node (ref "DA2") (pin "3") (pinfunction "VBAT_3") (pintype "passive"))
      (node (ref "VT1") (pin "2") (pinfunction "D_2") (pintype "passive"))
      (node (ref "XP24") (pin "1") (pinfunction "1_1") (pintype "passive"))
      (node (ref "XP27") (pin "1") (pinfunction "1_1") (pintype "passive"))
    )
    (net (code "48") (name "unconnected-(DD1-CBUS0-Pad12)") (class "Default")
      (node (ref "DD1") (pin "12") (pinfunction "CBUS0_12") (pintype "bidirectional+no_connect"))
    )
    (net (code "49") (name "unconnected-(DD1-CBUS1-Pad11)") (class "Default")
      (node (ref "DD1") (pin "11") (pinfunction "CBUS1_11") (pintype "bidirectional+no_connect"))
    )
    (net (code "50") (name "unconnected-(DD1-CBUS2-Pad5)") (class "Default")
      (node (ref "DD1") (pin "5") (pinfunction "CBUS2_5") (pintype "bidirectional+no_connect"))
    )
    (net (code "51") (name "unconnected-(DD1-CBUS3-Pad14)") (class "Default")
      (node (ref "DD1") (pin "14") (pinfunction "CBUS3_14") (pintype "bidirectional+no_connect"))
    )
    (net (code "52") (name "unconnected-(XP1-Pad3)") (class "Default")
      (node (ref "XP1") (pin "3") (pinfunction "3_3") (pintype "passive+no_connect"))
    )
    (net (code "53") (name "unconnected-(XP1-Pad4)") (class "Default")
      (node (ref "XP1") (pin "4") (pinfunction "4_4") (pintype "passive+no_connect"))
    )
    (net (code "54") (name "unconnected-(XP1-Pad5)") (class "Default")
      (node (ref "XP1") (pin "5") (pinfunction "5_5") (pintype "passive"))
    )
    (net (code "55") (name "unconnected-(XS1-Pad4)") (class "Default")
      (node (ref "XS1") (pin "4") (pinfunction "4_4") (pintype "passive"))
    )
  )
)
